# 1-WireHumidity.net
KiCad netlist of a schematic drawn in EAGLE
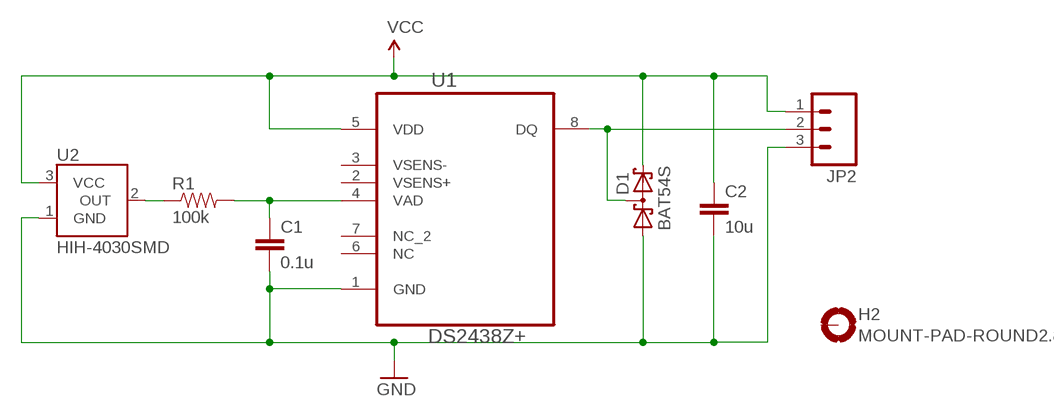
[diagram p0: schematic, sheet 1]

(export (version "E")
  (design (tool "Eeschema 10.0.6"))
  (components
    (comp (ref "C1")
      (value "0.1u")
      (footprint "eagle-import:0603-CAP")
      (libsource (lib "eagle-import") (part "CAP0603-CAP"))
    )
    (comp (ref "C2")
      (value "10u")
      (footprint "eagle-import:0603-CAP")
      (libsource (lib "eagle-import") (part "CAP0603-CAP"))
    )
    (comp (ref "D1")
      (value "BAT54S")
      (footprint "eagle-import:SOT23")
      (libsource (lib "eagle-import") (part "BAT54S"))
    )
    (comp (ref "H2")
      (value "MOUNT-PAD-ROUND2.8")
      (footprint "eagle-import:2,8-PAD")
      (libsource (lib "eagle-import") (part "MOUNT-PAD-ROUND2.8"))
    )
    (comp (ref "JP2")
      (value "M03LONGPADS")
      (footprint "eagle-import:1X03_LONGPADS")
      (libsource (lib "eagle-import") (part "M03LONGPADS"))
    )
    (comp (ref "R1")
      (value "100k")
      (footprint "eagle-import:0603-RES")
      (libsource (lib "eagle-import") (part "RESISTOR0603-RES"))
    )
    (comp (ref "U1")
      (value "DS2438Z+")
      (footprint "eagle-import:SOIC127P600X175-8N")
      (libsource (lib "eagle-import") (part "DS2438Z+"))
    )
    (comp (ref "U2")
      (value "HIH-4030SMD")
      (footprint "eagle-import:HIH-4030")
      (libsource (lib "eagle-import") (part "HIH-4030SMD"))
    )
  )
  (nets
    (net (code "1") (name "GND") (class "Default")
      (node (ref "C1") (pin "2") (pinfunction "2_2") (pintype "passive"))
      (node (ref "C2") (pin "2") (pinfunction "2_2") (pintype "passive"))
      (node (ref "D1") (pin "1") (pinfunction "A1_1") (pintype "passive"))
      (node (ref "JP2") (pin "3") (pinfunction "3_3") (pintype "passive"))
      (node (ref "U1") (pin "1") (pinfunction "GND_1") (pintype "passive"))
      (node (ref "U2") (pin "1") (pinfunction "GND_1") (pintype "bidirectional"))
    )
    (net (code "2") (name "Net-(D1-C1A2)") (class "Default")
      (node (ref "D1") (pin "3") (pinfunction "C1A2_3") (pintype "passive"))
      (node (ref "JP2") (pin "2") (pinfunction "2_2") (pintype "passive"))
      (node (ref "U1") (pin "8") (pinfunction "DQ_8") (pintype "bidirectional"))
    )
    (net (code "3") (name "Net-(U1-VAD)") (class "Default")
      (node (ref "C1") (pin "1") (pinfunction "1_1") (pintype "passive"))
      (node (ref "R1") (pin "2") (pinfunction "2_2") (pintype "passive"))
      (node (ref "U1") (pin "4") (pinfunction "VAD_4") (pintype "input"))
    )
    (net (code "4") (name "Net-(U2-OUT)") (class "Default")
      (node (ref "R1") (pin "1") (pinfunction "1_1") (pintype "passive"))
      (node (ref "U2") (pin "2") (pinfunction "OUT_2") (pintype "bidirectional"))
    )
    (net (code "5") (name "VCC") (class "Default")
      (node (ref "C2") (pin "1") (pinfunction "1_1") (pintype "passive"))
      (node (ref "D1") (pin "2") (pinfunction "C2_2") (pintype "passive"))
      (node (ref "JP2") (pin "1") (pinfunction "1_1") (pintype "passive"))
      (node (ref "U1") (pin "5") (pinfunction "VDD_5") (pintype "power_in"))
      (node (ref "U2") (pin "3") (pinfunction "VCC_3") (pintype "bidirectional"))
    )
    (net (code "6") (name "unconnected-(H2-MOUNT-PadB2,8)") (class "Default")
      (node (ref "H2") (pin "B2,8") (pinfunction "MOUNT_B2,8") (pintype "passive"))
    )
    (net (code "7") (name "unconnected-(U1-NC-Pad6)") (class "Default")
      (node (ref "U1") (pin "6") (pinfunction "NC_6") (pintype "no_connect"))
    )
    (net (code "8") (name "unconnected-(U1-NC_2-Pad7)") (class "Default")
      (node (ref "U1") (pin "7") (pinfunction "NC_2_7") (pintype "no_connect"))
    )
    (net (code "9") (name "unconnected-(U1-VSENS+-Pad2)") (class "Default")
      (node (ref "U1") (pin "2") (pinfunction "VSENS+_2") (pintype "input"))
    )
    (net (code "10") (name "unconnected-(U1-VSENS--Pad3)") (class "Default")
      (node (ref "U1") (pin "3") (pinfunction "VSENS-_3") (pintype "input"))
    )
  )
)
